# 7-IO_Headers.net
KiCad netlist of a schematic drawn in Altium Designer
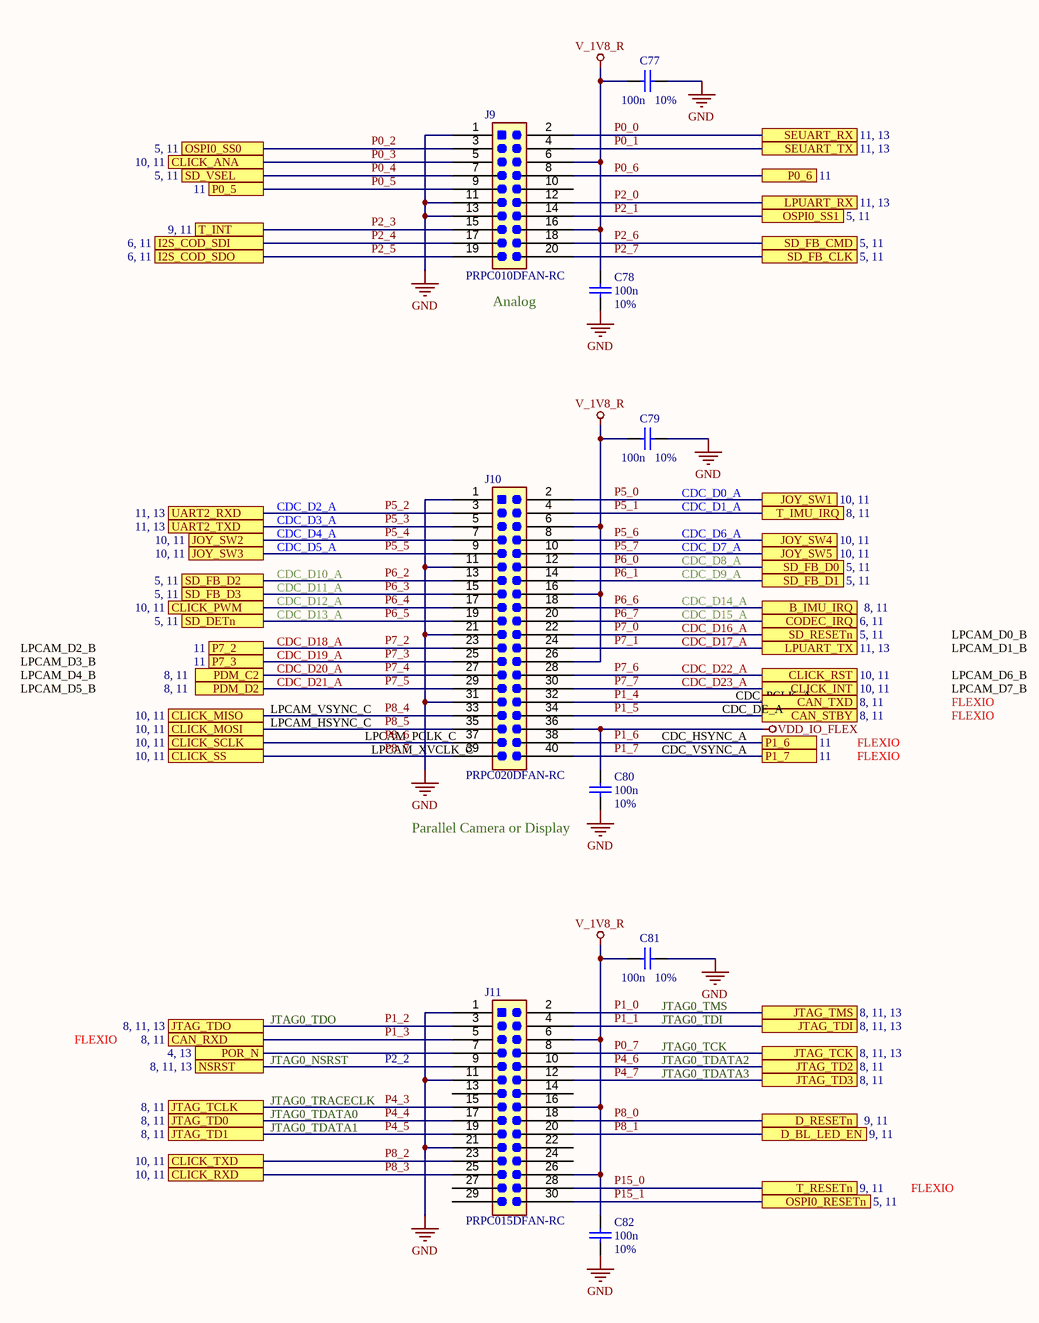
[diagram p0: 7-IO_Headers.SchDoc]

(export (version "E")
  (design (tool "Eeschema 10.0.6"))
  (components
    (comp (ref "C77")
      (value "100n")
      (footprint "CAPC0402-01")
      (description "Cap,100nF,10%,50V,X7R,0402")
      (fields
        (field (name "VOLTAGE") "50V")
        (field (name "TOLERANCE") "10%")
        (field (name "Comment") "Cap")
        (field (name "PUBLISHER") "Altium Limited")
      )
      (libsource (lib "kb1") (part "Cap"))
    )
    (comp (ref "C78")
      (value "100n")
      (footprint "CAPC0402-01")
      (description "Cap,100nF,10%,50V,X7R,0402")
      (fields
        (field (name "VOLTAGE") "50V")
        (field (name "TOLERANCE") "10%")
        (field (name "Comment") "Cap")
        (field (name "PUBLISHER") "Altium Limited")
      )
      (libsource (lib "kb1") (part "Cap"))
    )
    (comp (ref "C79")
      (value "100n")
      (footprint "CAPC0402-01")
      (description "Cap,100nF,10%,50V,X7R,0402")
      (fields
        (field (name "VOLTAGE") "50V")
        (field (name "TOLERANCE") "10%")
        (field (name "Comment") "Cap")
        (field (name "PUBLISHER") "Altium Limited")
      )
      (libsource (lib "kb1") (part "Cap"))
    )
    (comp (ref "C80")
      (value "100n")
      (footprint "CAPC0402-01")
      (description "Cap,100nF,10%,50V,X7R,0402")
      (fields
        (field (name "VOLTAGE") "50V")
        (field (name "TOLERANCE") "10%")
        (field (name "Comment") "Cap")
        (field (name "PUBLISHER") "Altium Limited")
      )
      (libsource (lib "kb1") (part "Cap"))
    )
    (comp (ref "C81")
      (value "100n")
      (footprint "CAPC0402-01")
      (description "Cap,100nF,10%,50V,X7R,0402")
      (fields
        (field (name "VOLTAGE") "50V")
        (field (name "TOLERANCE") "10%")
        (field (name "Comment") "Cap")
        (field (name "PUBLISHER") "Altium Limited")
      )
      (libsource (lib "kb1") (part "Cap"))
    )
    (comp (ref "C82")
      (value "100n")
      (footprint "CAPC0402-01")
      (description "Cap,100nF,10%,50V,X7R,0402")
      (fields
        (field (name "VOLTAGE") "50V")
        (field (name "TOLERANCE") "10%")
        (field (name "Comment") "Cap")
        (field (name "PUBLISHER") "Altium Limited")
      )
      (libsource (lib "kb1") (part "Cap"))
    )
    (comp (ref "J9")
      (value "PRPC010DFAN-RC")
      (footprint "CON20_2X10_P100UM_HDR_TYC")
      (description "Hdr, Male,2x10, 0.1\"x0.1\", Strt,Mate Ht 0.318\",Tail Ht 0.120\",Unshrouded")
      (libsource (lib "Alif-2") (part "Hdr_M_2X10_2M54_STRT_UNSHROUDED"))
    )
    (comp (ref "J10")
      (value "PRPC020DFAN-RC")
      (footprint "CON40_2X20_P100UM_HDR_TYC")
      (description "Hdr, Male,2x20, 0.1\"x0.1\", Strt,Mate Ht 0.318\",Tail Ht 0.120\",Unshrouded")
      (libsource (lib "Alif-2") (part "Hdr_M_2X20_2M54_STRT_UNSHROUDED"))
    )
    (comp (ref "J11")
      (value "PRPC015DFAN-RC")
      (footprint "CON30_2X15_P100UM_HDR_TYC")
      (description "Hdr, Male,2x15, 0.1\"x0.1\", Strt,Mate Ht 0.318\",Tail Ht 0.120\",Unshrouded")
      (libsource (lib "Alif-2") (part "Hdr_M_2X15_2M54_STRT_UNSHROUDED"))
    )
  )
  (nets
    (net (code "1") (name "/NSRST") (class "Default")
      (node (ref "J11") (pin "9") (pinfunction "9_9") (pintype "passive"))
    )
    (net (code "2") (name "/P0_0") (class "Default")
      (node (ref "J9") (pin "2") (pinfunction "2_2") (pintype "passive"))
    )
    (net (code "3") (name "/P0_1") (class "Default")
      (node (ref "J9") (pin "4") (pinfunction "4_4") (pintype "passive"))
    )
    (net (code "4") (name "/P0_2") (class "Default")
      (node (ref "J9") (pin "3") (pinfunction "3_3") (pintype "passive"))
    )
    (net (code "5") (name "/P0_3") (class "Default")
      (node (ref "J9") (pin "5") (pinfunction "5_5") (pintype "passive"))
    )
    (net (code "6") (name "/P0_4") (class "Default")
      (node (ref "J9") (pin "7") (pinfunction "7_7") (pintype "passive"))
    )
    (net (code "7") (name "/P0_5") (class "Default")
      (node (ref "J9") (pin "9") (pinfunction "9_9") (pintype "passive"))
    )
    (net (code "8") (name "/P0_6") (class "Default")
      (node (ref "J9") (pin "8") (pinfunction "8_8") (pintype "passive"))
    )
    (net (code "9") (name "/P0_7") (class "Default")
      (node (ref "J11") (pin "8") (pinfunction "8_8") (pintype "passive"))
    )
    (net (code "10") (name "/P1_0") (class "Default")
      (node (ref "J11") (pin "2") (pinfunction "2_2") (pintype "passive"))
    )
    (net (code "11") (name "/P1_1") (class "Default")
      (node (ref "J11") (pin "4") (pinfunction "4_4") (pintype "passive"))
    )
    (net (code "12") (name "/P1_2") (class "Default")
      (node (ref "J11") (pin "3") (pinfunction "3_3") (pintype "passive"))
    )
    (net (code "13") (name "/P1_3") (class "Default")
      (node (ref "J11") (pin "5") (pinfunction "5_5") (pintype "passive"))
    )
    (net (code "14") (name "/P1_4") (class "Default")
      (node (ref "J10") (pin "32") (pinfunction "32_32") (pintype "passive"))
    )
    (net (code "15") (name "/P1_5") (class "Default")
      (node (ref "J10") (pin "34") (pinfunction "34_34") (pintype "passive"))
    )
    (net (code "16") (name "/P1_6") (class "Default")
      (node (ref "J10") (pin "38") (pinfunction "38_38") (pintype "passive"))
    )
    (net (code "17") (name "/P1_7") (class "Default")
      (node (ref "J10") (pin "40") (pinfunction "40_40") (pintype "passive"))
    )
    (net (code "18") (name "/P2_0") (class "Default")
      (node (ref "J9") (pin "12") (pinfunction "12_12") (pintype "passive"))
    )
    (net (code "19") (name "/P2_1") (class "Default")
      (node (ref "J9") (pin "14") (pinfunction "14_14") (pintype "passive"))
    )
    (net (code "20") (name "/P2_3") (class "Default")
      (node (ref "J9") (pin "15") (pinfunction "15_15") (pintype "passive"))
    )
    (net (code "21") (name "/P2_4") (class "Default")
      (node (ref "J9") (pin "17") (pinfunction "17_17") (pintype "passive"))
    )
    (net (code "22") (name "/P2_5") (class "Default")
      (node (ref "J9") (pin "19") (pinfunction "19_19") (pintype "passive"))
    )
    (net (code "23") (name "/P2_6") (class "Default")
      (node (ref "J9") (pin "18") (pinfunction "18_18") (pintype "passive"))
    )
    (net (code "24") (name "/P2_7") (class "Default")
      (node (ref "J9") (pin "20") (pinfunction "20_20") (pintype "passive"))
    )
    (net (code "25") (name "/P4_3") (class "Default")
      (node (ref "J11") (pin "15") (pinfunction "15_15") (pintype "passive"))
    )
    (net (code "26") (name "/P4_4") (class "Default")
      (node (ref "J11") (pin "17") (pinfunction "17_17") (pintype "passive"))
    )
    (net (code "27") (name "/P4_5") (class "Default")
      (node (ref "J11") (pin "19") (pinfunction "19_19") (pintype "passive"))
    )
    (net (code "28") (name "/P4_6") (class "Default")
      (node (ref "J11") (pin "10") (pinfunction "10_10") (pintype "passive"))
    )
    (net (code "29") (name "/P4_7") (class "Default")
      (node (ref "J11") (pin "12") (pinfunction "12_12") (pintype "passive"))
    )
    (net (code "30") (name "/P5_0") (class "Default")
      (node (ref "J10") (pin "2") (pinfunction "2_2") (pintype "passive"))
    )
    (net (code "31") (name "/P5_1") (class "Default")
      (node (ref "J10") (pin "4") (pinfunction "4_4") (pintype "passive"))
    )
    (net (code "32") (name "/P5_2") (class "Default")
      (node (ref "J10") (pin "3") (pinfunction "3_3") (pintype "passive"))
    )
    (net (code "33") (name "/P5_3") (class "Default")
      (node (ref "J10") (pin "5") (pinfunction "5_5") (pintype "passive"))
    )
    (net (code "34") (name "/P5_4") (class "Default")
      (node (ref "J10") (pin "7") (pinfunction "7_7") (pintype "passive"))
    )
    (net (code "35") (name "/P5_5") (class "Default")
      (node (ref "J10") (pin "9") (pinfunction "9_9") (pintype "passive"))
    )
    (net (code "36") (name "/P5_6") (class "Default")
      (node (ref "J10") (pin "8") (pinfunction "8_8") (pintype "passive"))
    )
    (net (code "37") (name "/P5_7") (class "Default")
      (node (ref "J10") (pin "10") (pinfunction "10_10") (pintype "passive"))
    )
    (net (code "38") (name "/P6_0") (class "Default")
      (node (ref "J10") (pin "12") (pinfunction "12_12") (pintype "passive"))
    )
    (net (code "39") (name "/P6_1") (class "Default")
      (node (ref "J10") (pin "14") (pinfunction "14_14") (pintype "passive"))
    )
    (net (code "40") (name "/P6_2") (class "Default")
      (node (ref "J10") (pin "13") (pinfunction "13_13") (pintype "passive"))
    )
    (net (code "41") (name "/P6_3") (class "Default")
      (node (ref "J10") (pin "15") (pinfunction "15_15") (pintype "passive"))
    )
    (net (code "42") (name "/P6_4") (class "Default")
      (node (ref "J10") (pin "17") (pinfunction "17_17") (pintype "passive"))
    )
    (net (code "43") (name "/P6_5") (class "Default")
      (node (ref "J10") (pin "19") (pinfunction "19_19") (pintype "passive"))
    )
    (net (code "44") (name "/P6_6") (class "Default")
      (node (ref "J10") (pin "18") (pinfunction "18_18") (pintype "passive"))
    )
    (net (code "45") (name "/P6_7") (class "Default")
      (node (ref "J10") (pin "20") (pinfunction "20_20") (pintype "passive"))
    )
    (net (code "46") (name "/P7_0") (class "Default")
      (node (ref "J10") (pin "22") (pinfunction "22_22") (pintype "passive"))
    )
    (net (code "47") (name "/P7_1") (class "Default")
      (node (ref "J10") (pin "24") (pinfunction "24_24") (pintype "passive"))
    )
    (net (code "48") (name "/P7_2") (class "Default")
      (node (ref "J10") (pin "23") (pinfunction "23_23") (pintype "passive"))
    )
    (net (code "49") (name "/P7_3") (class "Default")
      (node (ref "J10") (pin "25") (pinfunction "25_25") (pintype "passive"))
    )
    (net (code "50") (name "/P7_4") (class "Default")
      (node (ref "J10") (pin "27") (pinfunction "27_27") (pintype "passive"))
    )
    (net (code "51") (name "/P7_5") (class "Default")
      (node (ref "J10") (pin "29") (pinfunction "29_29") (pintype "passive"))
    )
    (net (code "52") (name "/P7_6") (class "Default")
      (node (ref "J10") (pin "28") (pinfunction "28_28") (pintype "passive"))
    )
    (net (code "53") (name "/P7_7") (class "Default")
      (node (ref "J10") (pin "30") (pinfunction "30_30") (pintype "passive"))
    )
    (net (code "54") (name "/P8_0") (class "Default")
      (node (ref "J11") (pin "18") (pinfunction "18_18") (pintype "passive"))
    )
    (net (code "55") (name "/P8_1") (class "Default")
      (node (ref "J11") (pin "20") (pinfunction "20_20") (pintype "passive"))
    )
    (net (code "56") (name "/P8_2") (class "Default")
      (node (ref "J11") (pin "23") (pinfunction "23_23") (pintype "passive"))
    )
    (net (code "57") (name "/P8_3") (class "Default")
      (node (ref "J11") (pin "25") (pinfunction "25_25") (pintype "passive"))
    )
    (net (code "58") (name "/P8_4") (class "Default")
      (node (ref "J10") (pin "33") (pinfunction "33_33") (pintype "passive"))
    )
    (net (code "59") (name "/P8_5") (class "Default")
      (node (ref "J10") (pin "35") (pinfunction "35_35") (pintype "passive"))
    )
    (net (code "60") (name "/P8_6") (class "Default")
      (node (ref "J10") (pin "37") (pinfunction "37_37") (pintype "passive"))
    )
    (net (code "61") (name "/P8_7") (class "Default")
      (node (ref "J10") (pin "39") (pinfunction "39_39") (pintype "passive"))
    )
    (net (code "62") (name "/P15_0") (class "Default")
      (node (ref "J11") (pin "28") (pinfunction "28_28") (pintype "passive"))
    )
    (net (code "63") (name "/P15_1") (class "Default")
      (node (ref "J11") (pin "30") (pinfunction "30_30") (pintype "passive"))
    )
    (net (code "64") (name "/POR_N") (class "Default")
      (node (ref "J11") (pin "7") (pinfunction "7_7") (pintype "passive"))
    )
    (net (code "65") (name "GND") (class "Default")
      (node (ref "C77") (pin "1") (pinfunction "1_1") (pintype "passive"))
      (node (ref "C78") (pin "1") (pinfunction "1_1") (pintype "passive"))
      (node (ref "C79") (pin "1") (pinfunction "1_1") (pintype "passive"))
      (node (ref "C80") (pin "1") (pinfunction "1_1") (pintype "passive"))
      (node (ref "C81") (pin "1") (pinfunction "1_1") (pintype "passive"))
      (node (ref "C82") (pin "1") (pinfunction "1_1") (pintype "passive"))
      (node (ref "J10") (pin "1") (pinfunction "1_1") (pintype "passive"))
      (node (ref "J10") (pin "11") (pinfunction "11_11") (pintype "passive"))
      (node (ref "J10") (pin "21") (pinfunction "21_21") (pintype "passive"))
      (node (ref "J10") (pin "31") (pinfunction "31_31") (pintype "passive"))
      (node (ref "J11") (pin "1") (pinfunction "1_1") (pintype "passive"))
      (node (ref "J11") (pin "11") (pinfunction "11_11") (pintype "passive"))
      (node (ref "J11") (pin "21") (pinfunction "21_21") (pintype "passive"))
      (node (ref "J9") (pin "1") (pinfunction "1_1") (pintype "passive"))
      (node (ref "J9") (pin "11") (pinfunction "11_11") (pintype "passive"))
      (node (ref "J9") (pin "13") (pinfunction "13_13") (pintype "passive"))
    )
    (net (code "66") (name "VDD_IO_FLEX") (class "Default")
      (node (ref "C80") (pin "2") (pinfunction "2_2") (pintype "passive"))
      (node (ref "J10") (pin "36") (pinfunction "36_36") (pintype "passive"))
    )
    (net (code "67") (name "V_1V8_R") (class "Default")
      (node (ref "C77") (pin "2") (pinfunction "2_2") (pintype "passive"))
      (node (ref "C78") (pin "2") (pinfunction "2_2") (pintype "passive"))
      (node (ref "C79") (pin "2") (pinfunction "2_2") (pintype "passive"))
      (node (ref "C81") (pin "2") (pinfunction "2_2") (pintype "passive"))
      (node (ref "C82") (pin "2") (pinfunction "2_2") (pintype "passive"))
      (node (ref "J10") (pin "16") (pinfunction "16_16") (pintype "passive"))
      (node (ref "J10") (pin "26") (pinfunction "26_26") (pintype "passive"))
      (node (ref "J10") (pin "6") (pinfunction "6_6") (pintype "passive"))
      (node (ref "J11") (pin "16") (pinfunction "16_16") (pintype "passive"))
      (node (ref "J11") (pin "26") (pinfunction "26_26") (pintype "passive"))
      (node (ref "J11") (pin "6") (pinfunction "6_6") (pintype "passive"))
      (node (ref "J9") (pin "16") (pinfunction "16_16") (pintype "passive"))
      (node (ref "J9") (pin "6") (pinfunction "6_6") (pintype "passive"))
    )
    (net (code "68") (name "unconnected-(J9-Pad10)") (class "Default")
      (node (ref "J9") (pin "10") (pinfunction "10_10") (pintype "passive"))
    )
    (net (code "69") (name "unconnected-(J11-Pad13)") (class "Default")
      (node (ref "J11") (pin "13") (pinfunction "13_13") (pintype "passive"))
    )
    (net (code "70") (name "unconnected-(J11-Pad14)") (class "Default")
      (node (ref "J11") (pin "14") (pinfunction "14_14") (pintype "passive"))
    )
    (net (code "71") (name "unconnected-(J11-Pad22)") (class "Default")
      (node (ref "J11") (pin "22") (pinfunction "22_22") (pintype "passive"))
    )
    (net (code "72") (name "unconnected-(J11-Pad24)") (class "Default")
      (node (ref "J11") (pin "24") (pinfunction "24_24") (pintype "passive"))
    )
    (net (code "73") (name "unconnected-(J11-Pad27)") (class "Default")
      (node (ref "J11") (pin "27") (pinfunction "27_27") (pintype "passive"))
    )
    (net (code "74") (name "unconnected-(J11-Pad29)") (class "Default")
      (node (ref "J11") (pin "29") (pinfunction "29_29") (pintype "passive"))
    )
  )
)
